# FPGA_CONFIG.net
KiCad netlist of a schematic drawn in Altium Designer
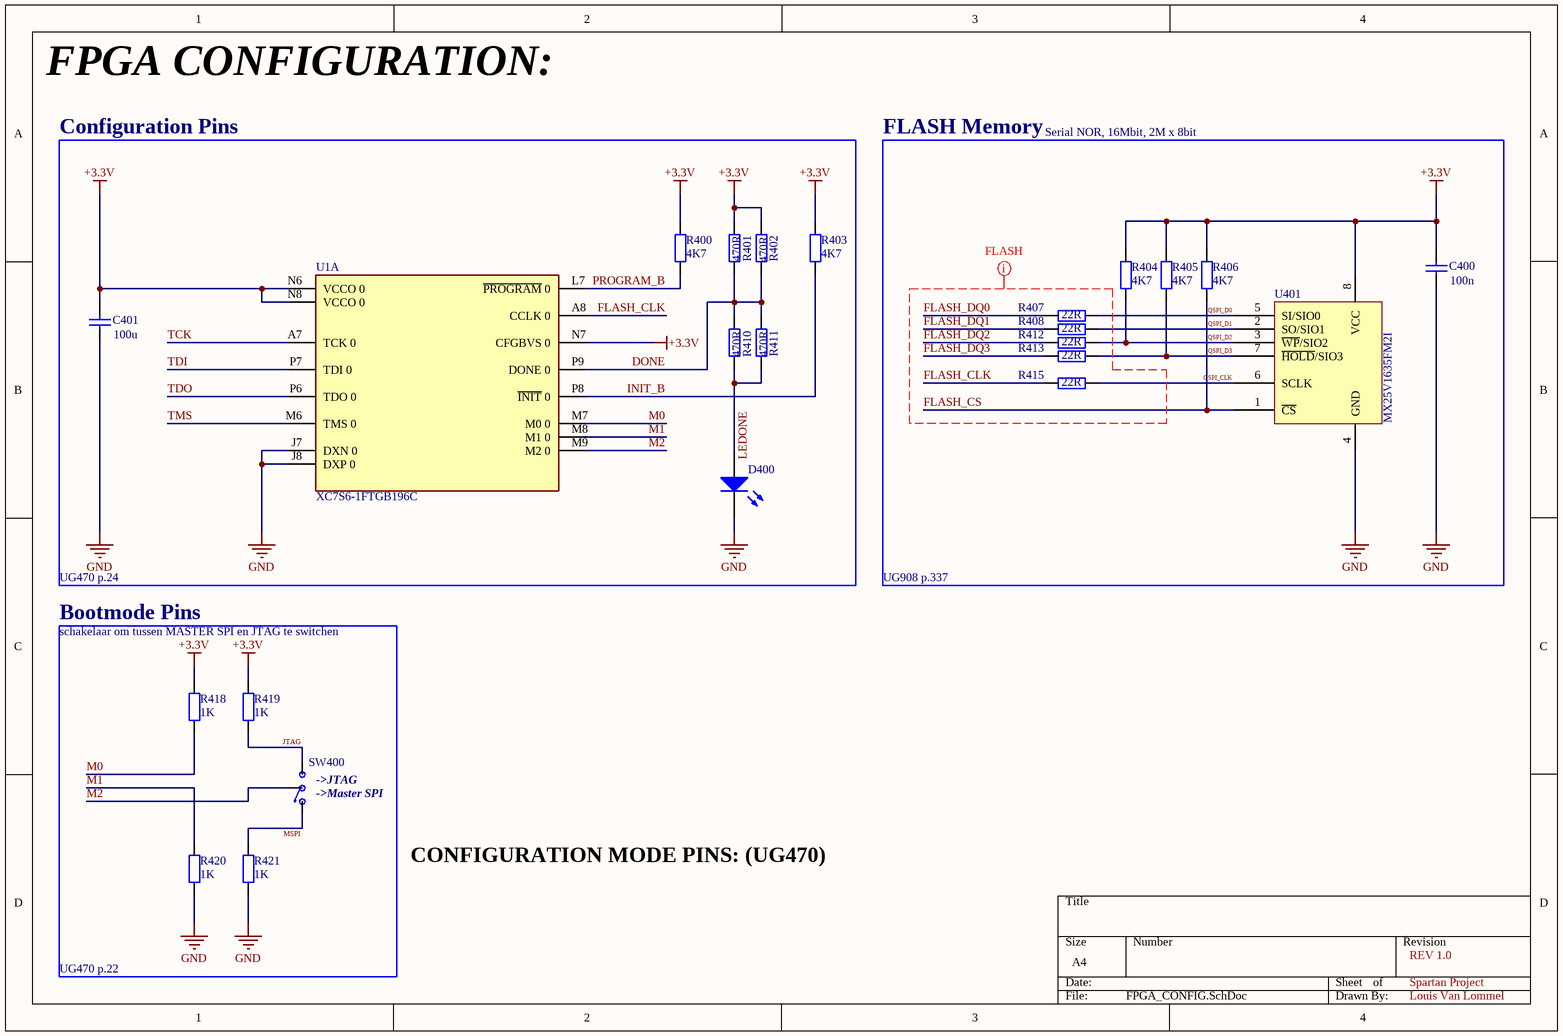
[diagram p0: FPGA_CONFIG.SchDoc]

(export (version "E")
  (design (tool "Eeschema 10.0.6"))
  (components
    (comp (ref "C400")
      (value "100n")
      (footprint "CAP_0603")
      (description "Capacitor")
      (fields (field (name "PUBLISHER") "Altium Limited"))
      (libsource (lib "Miscellaneous Devices") (part "Cap"))
    )
    (comp (ref "C401")
      (value "100u")
      (footprint "CAP_0805")
      (description "Capacitor")
      (fields (field (name "Comment") "100uF") (field (name "PUBLISHER") "Altium Limited"))
      (libsource (lib "Miscellaneous Devices") (part "Cap"))
    )
    (comp (ref "D400")
      (value "LED")
      (footprint "LED_0603")
      (description "Typical INFRARED GaAs LED")
      (fields (field (name "PUBLISHER") "Altium Limited"))
      (libsource (lib "Miscellaneous Devices") (part "LED0"))
    )
    (comp (ref "R400")
      (value "4K7")
      (footprint "RES_0603")
      (description "Resistor")
      (fields (field (name "PUBLISHER") "Altium Limited"))
      (libsource (lib "") (part "Res2_1"))
    )
    (comp (ref "R401")
      (value "470R")
      (footprint "RES_0603")
      (description "Resistor")
      (fields (field (name "Comment") "470") (field (name "PUBLISHER") "Altium Limited"))
      (libsource (lib "") (part "Res2_1"))
    )
    (comp (ref "R402")
      (value "470R")
      (footprint "RES_0603")
      (description "Resistor")
      (fields (field (name "Comment") "470") (field (name "PUBLISHER") "Altium Limited"))
      (libsource (lib "") (part "Res2_1"))
    )
    (comp (ref "R403")
      (value "4K7")
      (footprint "RES_0603")
      (description "Resistor")
      (fields (field (name "PUBLISHER") "Altium Limited"))
      (libsource (lib "") (part "Res2_1"))
    )
    (comp (ref "R404")
      (value "4K7")
      (footprint "RES_0603")
      (description "Resistor")
      (fields (field (name "PUBLISHER") "Altium Limited"))
      (libsource (lib "") (part "Res2_1"))
    )
    (comp (ref "R405")
      (value "4K7")
      (footprint "RES_0603")
      (description "Resistor")
      (fields (field (name "PUBLISHER") "Altium Limited"))
      (libsource (lib "") (part "Res2_1"))
    )
    (comp (ref "R406")
      (value "4K7")
      (footprint "RES_0603")
      (description "Resistor")
      (fields (field (name "PUBLISHER") "Altium Limited"))
      (libsource (lib "") (part "Res2_1"))
    )
    (comp (ref "R407")
      (value "22R")
      (footprint "RES_0603")
      (description "Resistor")
      (fields (field (name "Comment") "22") (field (name "PUBLISHER") "Altium Limited"))
      (libsource (lib "Miscellaneous Devices") (part "Res2"))
    )
    (comp (ref "R408")
      (value "22R")
      (footprint "RES_0603")
      (description "Resistor")
      (fields (field (name "Comment") "22") (field (name "PUBLISHER") "Altium Limited"))
      (libsource (lib "Miscellaneous Devices") (part "Res2"))
    )
    (comp (ref "R410")
      (value "470R")
      (footprint "RES_0603")
      (description "Resistor")
      (fields (field (name "Comment") "470") (field (name "PUBLISHER") "Altium Limited"))
      (libsource (lib "") (part "Res2_1"))
    )
    (comp (ref "R411")
      (value "470R")
      (footprint "RES_0603")
      (description "Resistor")
      (fields (field (name "Comment") "470") (field (name "PUBLISHER") "Altium Limited"))
      (libsource (lib "") (part "Res2_1"))
    )
    (comp (ref "R412")
      (value "22R")
      (footprint "RES_0603")
      (description "Resistor")
      (fields (field (name "Comment") "22") (field (name "PUBLISHER") "Altium Limited"))
      (libsource (lib "Miscellaneous Devices") (part "Res2"))
    )
    (comp (ref "R413")
      (value "22R")
      (footprint "RES_0603")
      (description "Resistor")
      (fields (field (name "Comment") "22") (field (name "PUBLISHER") "Altium Limited"))
      (libsource (lib "Miscellaneous Devices") (part "Res2"))
    )
    (comp (ref "R415")
      (value "22R")
      (footprint "RES_0603")
      (description "Resistor")
      (fields (field (name "Comment") "22") (field (name "PUBLISHER") "Altium Limited"))
      (libsource (lib "Miscellaneous Devices") (part "Res2"))
    )
    (comp (ref "R418")
      (value "1K")
      (footprint "RES_0603")
      (description "Resistor")
      (fields (field (name "PUBLISHER") "Altium Limited"))
      (libsource (lib "") (part "Res2_1"))
    )
    (comp (ref "R419")
      (value "1K")
      (footprint "RES_0603")
      (description "Resistor")
      (fields (field (name "PUBLISHER") "Altium Limited"))
      (libsource (lib "") (part "Res2_1"))
    )
    (comp (ref "R420")
      (value "1K")
      (footprint "RES_0603")
      (description "Resistor")
      (fields (field (name "PUBLISHER") "Altium Limited"))
      (libsource (lib "") (part "Res2_1"))
    )
    (comp (ref "R421")
      (value "1K")
      (footprint "RES_0603")
      (description "Resistor")
      (fields (field (name "PUBLISHER") "Altium Limited"))
      (libsource (lib "") (part "Res2_1"))
    )
    (comp (ref "SW400")
      (value "SPDT SW")
      (footprint "SPDT SWITCH")
      (libsource (lib "Schematic_Symbols") (part "SPDT SW"))
    )
    (comp (ref "U1")
      (value "XC7S6-1FTGB196C")
      (footprint "FP-XC7S6-1FTGB196C-MFG")
      (fields
        (field (name "MANUFACTURER") "Xilinx")
        (field (name "OCTOPART") "https://octopart.com/xc7s6-1ftgb196c-xilinx-81890684")
      )
      (libsource (lib "Altium Content Vault") (part "4382e9425a5ef0cb43184b1739abe55"))
    )
    (comp (ref "U401")
      (value "MX25V1635FM2I")
      (footprint "SOP-8")
      (description "Flash Memory, Serial NOR, 16 Mbit, 2M x 8bit, SPI, SOP, 8 Pins")
      (libsource (lib "Schematic_Symbols") (part "MACRONIX MX25V1635FM2I"))
    )
  )
  (nets
    (net (code "1") (name "+3.3V") (class "Default")
      (node (ref "C400") (pin "2") (pinfunction "2_2") (pintype "passive"))
      (node (ref "C401") (pin "2") (pinfunction "2_2") (pintype "passive"))
      (node (ref "R400") (pin "2") (pinfunction "2_2") (pintype "passive"))
      (node (ref "R401") (pin "2") (pinfunction "2_2") (pintype "passive"))
      (node (ref "R402") (pin "2") (pinfunction "2_2") (pintype "passive"))
      (node (ref "R403") (pin "2") (pinfunction "2_2") (pintype "passive"))
      (node (ref "R404") (pin "2") (pinfunction "2_2") (pintype "passive"))
      (node (ref "R405") (pin "2") (pinfunction "2_2") (pintype "passive"))
      (node (ref "R406") (pin "2") (pinfunction "2_2") (pintype "passive"))
      (node (ref "R418") (pin "2") (pinfunction "2_2") (pintype "passive"))
      (node (ref "R419") (pin "2") (pinfunction "2_2") (pintype "passive"))
      (node (ref "U1") (pin "N6") (pinfunction "VCCO_0_N6") (pintype "passive"))
      (node (ref "U1") (pin "N7") (pinfunction "CFGBVS_0_N7") (pintype "passive"))
      (node (ref "U1") (pin "N8") (pinfunction "VCCO_0_N8") (pintype "passive"))
      (node (ref "U401") (pin "8") (pinfunction "VCC_8") (pintype "passive"))
    )
    (net (code "2") (name "/DONE") (class "Default")
      (node (ref "R401") (pin "1") (pinfunction "1_1") (pintype "passive"))
      (node (ref "R402") (pin "1") (pinfunction "1_1") (pintype "passive"))
      (node (ref "R410") (pin "2") (pinfunction "2_2") (pintype "passive"))
      (node (ref "R411") (pin "2") (pinfunction "2_2") (pintype "passive"))
      (node (ref "U1") (pin "P9") (pinfunction "DONE_0_P9") (pintype "passive"))
    )
    (net (code "3") (name "/FLASH_CLK") (class "Default")
      (node (ref "R415") (pin "2") (pinfunction "2_2") (pintype "passive"))
      (node (ref "U1") (pin "A8") (pinfunction "CCLK_0_A8") (pintype "passive"))
    )
    (net (code "4") (name "/FLASH_CS") (class "Default")
      (node (ref "R406") (pin "1") (pinfunction "1_1") (pintype "passive"))
      (node (ref "U401") (pin "1") (pinfunction "~{CS}_1") (pintype "passive"))
    )
    (net (code "5") (name "/FLASH_DQ0") (class "Default")
      (node (ref "R407") (pin "2") (pinfunction "2_2") (pintype "passive"))
    )
    (net (code "6") (name "/FLASH_DQ1") (class "Default")
      (node (ref "R408") (pin "2") (pinfunction "2_2") (pintype "passive"))
    )
    (net (code "7") (name "/FLASH_DQ2") (class "Default")
      (node (ref "R412") (pin "2") (pinfunction "2_2") (pintype "passive"))
    )
    (net (code "8") (name "/FLASH_DQ3") (class "Default")
      (node (ref "R413") (pin "2") (pinfunction "2_2") (pintype "passive"))
    )
    (net (code "9") (name "/INIT_B") (class "Default")
      (node (ref "R403") (pin "1") (pinfunction "1_1") (pintype "passive"))
      (node (ref "U1") (pin "P8") (pinfunction "~{INIT}_0_P8") (pintype "passive"))
    )
    (net (code "10") (name "/JTAG") (class "Default")
      (node (ref "R419") (pin "1") (pinfunction "1_1") (pintype "passive"))
      (node (ref "SW400") (pin "1") (pinfunction "1_1") (pintype "passive"))
    )
    (net (code "11") (name "/LEDONE") (class "Default")
      (node (ref "D400") (pin "1") (pinfunction "A_1") (pintype "passive"))
      (node (ref "R410") (pin "1") (pinfunction "1_1") (pintype "passive"))
      (node (ref "R411") (pin "1") (pinfunction "1_1") (pintype "passive"))
    )
    (net (code "12") (name "/M0") (class "Default")
      (node (ref "R418") (pin "1") (pinfunction "1_1") (pintype "passive"))
      (node (ref "U1") (pin "M7") (pinfunction "M0_0_M7") (pintype "passive"))
    )
    (net (code "13") (name "/M1") (class "Default")
      (node (ref "R420") (pin "2") (pinfunction "2_2") (pintype "passive"))
      (node (ref "U1") (pin "M8") (pinfunction "M1_0_M8") (pintype "passive"))
    )
    (net (code "14") (name "/M2") (class "Default")
      (node (ref "SW400") (pin "2") (pinfunction "2_2") (pintype "passive"))
      (node (ref "U1") (pin "M9") (pinfunction "M2_0_M9") (pintype "passive"))
    )
    (net (code "15") (name "/MSPI") (class "Default")
      (node (ref "R421") (pin "2") (pinfunction "2_2") (pintype "passive"))
      (node (ref "SW400") (pin "3") (pinfunction "3_3") (pintype "passive"))
    )
    (net (code "16") (name "/PROGRAM_B") (class "Default")
      (node (ref "R400") (pin "1") (pinfunction "1_1") (pintype "passive"))
      (node (ref "U1") (pin "L7") (pinfunction "~{PROGRAM}_0_L7") (pintype "passive"))
    )
    (net (code "17") (name "/QSPI_CLK") (class "Default")
      (node (ref "R415") (pin "1") (pinfunction "1_1") (pintype "passive"))
      (node (ref "U401") (pin "6") (pinfunction "SCLK_6") (pintype "passive"))
    )
    (net (code "18") (name "/QSPI_D0") (class "Default")
      (node (ref "R407") (pin "1") (pinfunction "1_1") (pintype "passive"))
      (node (ref "U401") (pin "5") (pinfunction "SI/SIO0_5") (pintype "passive"))
    )
    (net (code "19") (name "/QSPI_D1") (class "Default")
      (node (ref "R408") (pin "1") (pinfunction "1_1") (pintype "passive"))
      (node (ref "U401") (pin "2") (pinfunction "SO/SIO1_2") (pintype "passive"))
    )
    (net (code "20") (name "/QSPI_D2") (class "Default")
      (node (ref "R404") (pin "1") (pinfunction "1_1") (pintype "passive"))
      (node (ref "R412") (pin "1") (pinfunction "1_1") (pintype "passive"))
      (node (ref "U401") (pin "3") (pinfunction "~{WP}/SIO2_3") (pintype "passive"))
    )
    (net (code "21") (name "/QSPI_D3") (class "Default")
      (node (ref "R405") (pin "1") (pinfunction "1_1") (pintype "passive"))
      (node (ref "R413") (pin "1") (pinfunction "1_1") (pintype "passive"))
      (node (ref "U401") (pin "7") (pinfunction "~{HOLD}/SIO3_7") (pintype "passive"))
    )
    (net (code "22") (name "/TCK") (class "Default")
      (node (ref "U1") (pin "A7") (pinfunction "TCK_0_A7") (pintype "passive"))
    )
    (net (code "23") (name "/TDI") (class "Default")
      (node (ref "U1") (pin "P7") (pinfunction "TDI_0_P7") (pintype "passive"))
    )
    (net (code "24") (name "/TDO") (class "Default")
      (node (ref "U1") (pin "P6") (pinfunction "TDO_0_P6") (pintype "passive"))
    )
    (net (code "25") (name "/TMS") (class "Default")
      (node (ref "U1") (pin "M6") (pinfunction "TMS_0_M6") (pintype "passive"))
    )
    (net (code "26") (name "GND") (class "Default")
      (node (ref "C400") (pin "1") (pinfunction "1_1") (pintype "passive"))
      (node (ref "C401") (pin "1") (pinfunction "1_1") (pintype "passive"))
      (node (ref "D400") (pin "2") (pinfunction "K_2") (pintype "passive"))
      (node (ref "R420") (pin "1") (pinfunction "1_1") (pintype "passive"))
      (node (ref "R421") (pin "1") (pinfunction "1_1") (pintype "passive"))
      (node (ref "U1") (pin "J7") (pinfunction "DXN_0_J7") (pintype "passive"))
      (node (ref "U1") (pin "J8") (pinfunction "DXP_0_J8") (pintype "passive"))
      (node (ref "U401") (pin "4") (pinfunction "GND_4") (pintype "passive"))
    )
  )
)
